# DE-290817_01.net
KiCad netlist of a schematic drawn in Altium Designer
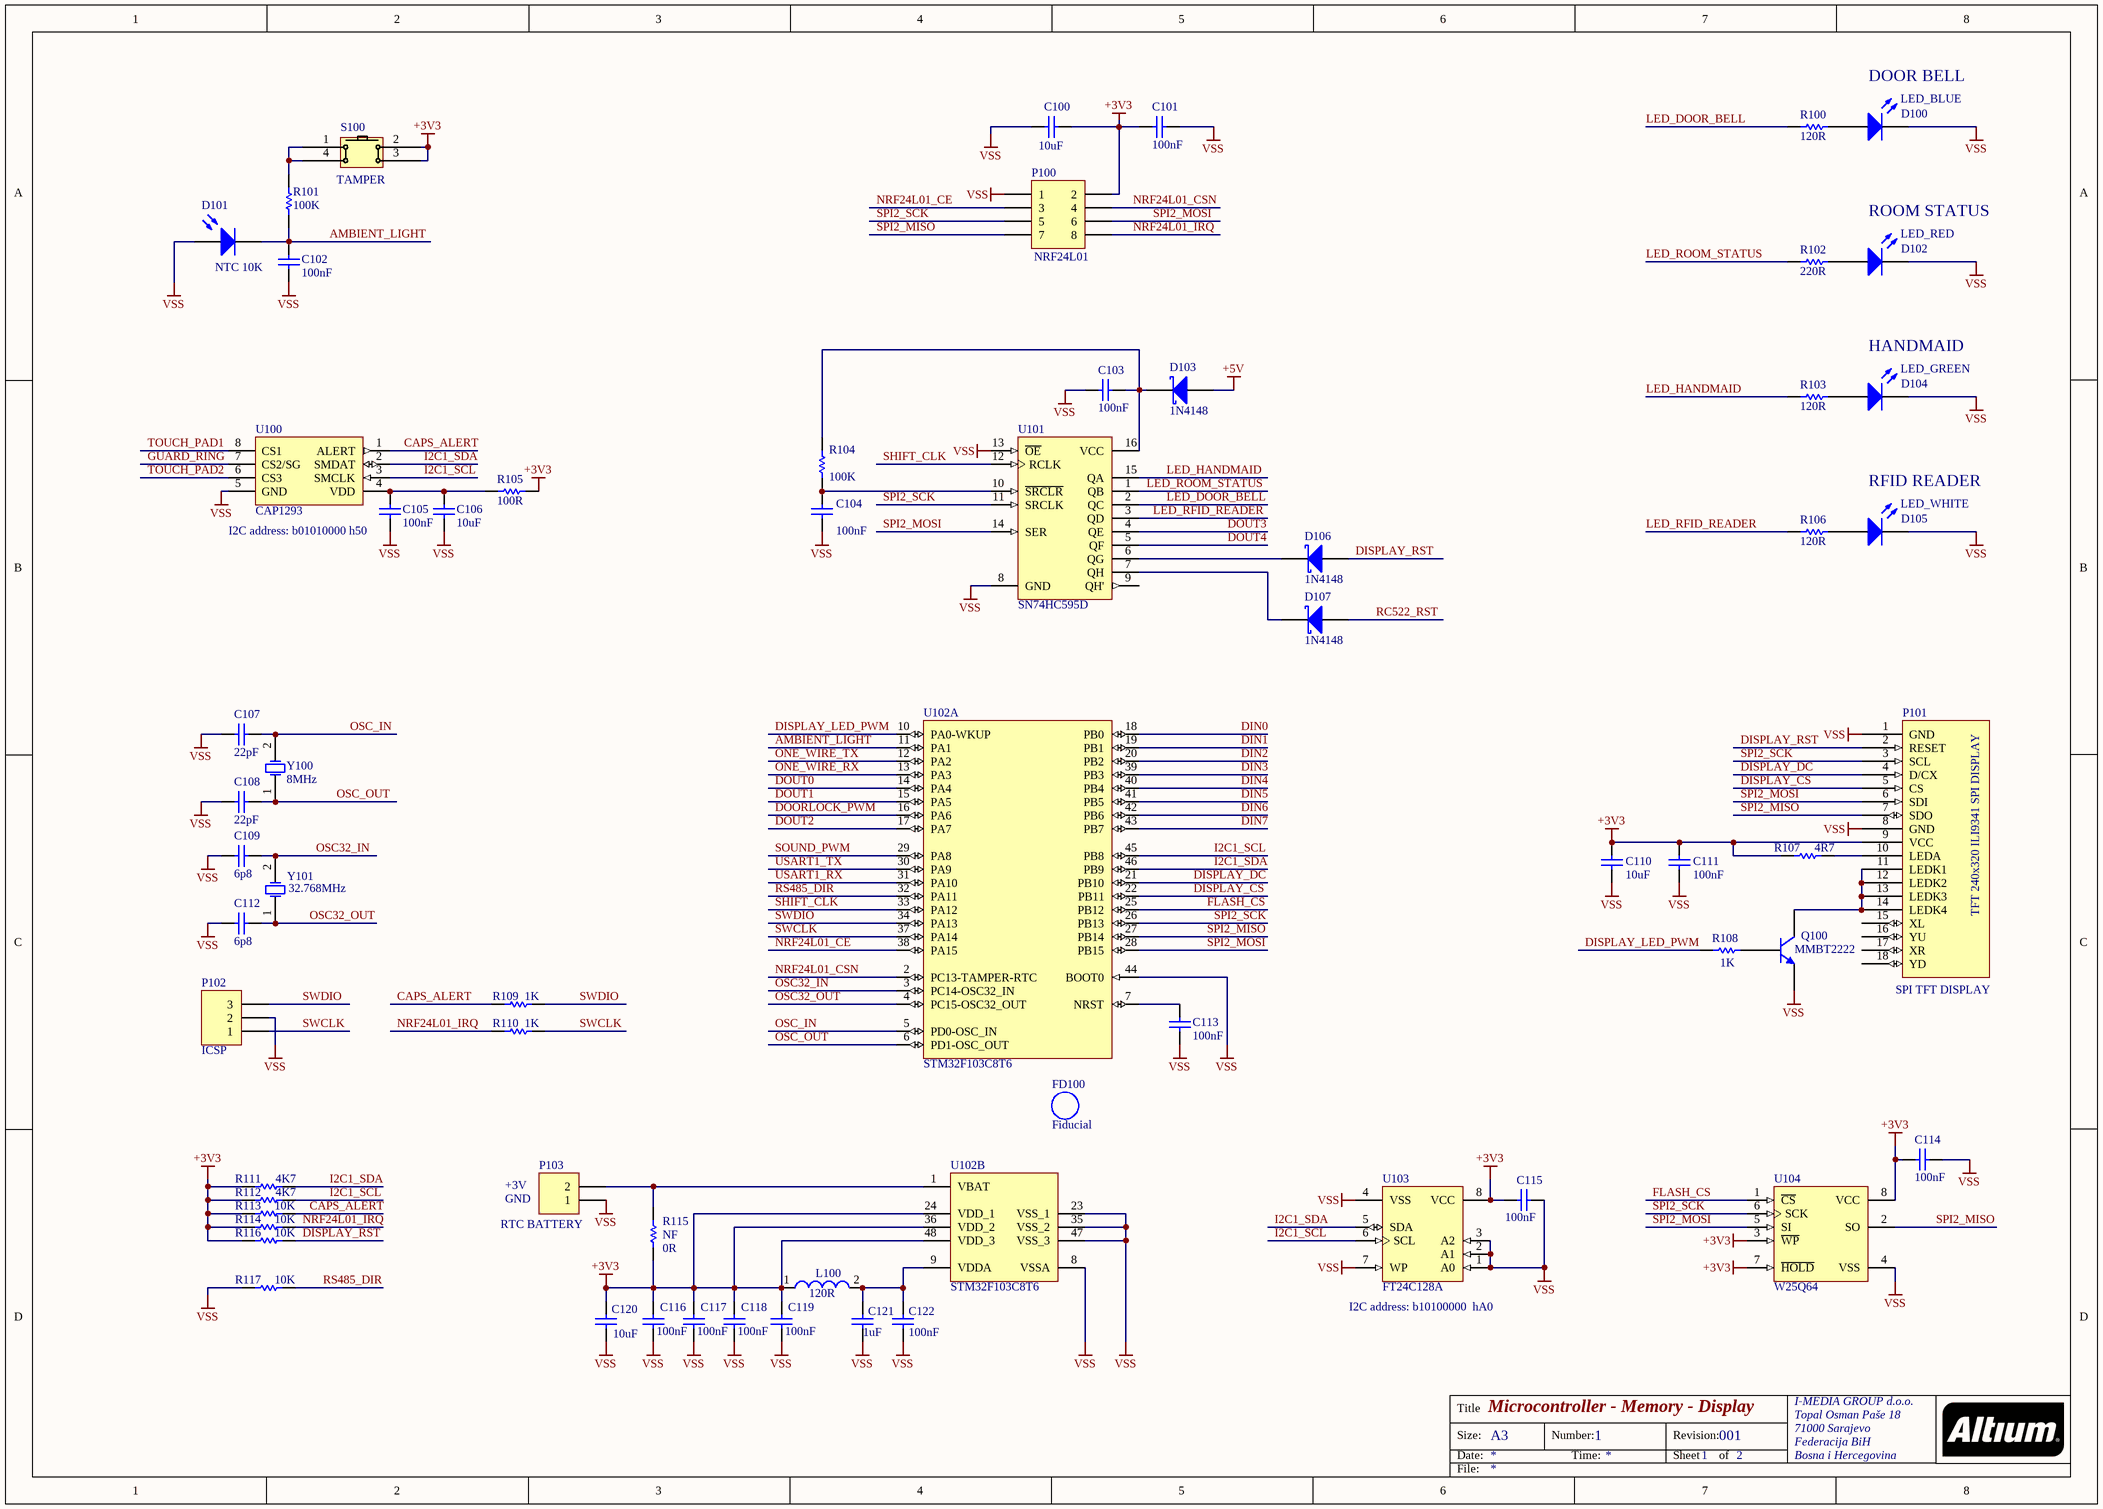
[diagram p0: DE-290817_01.SchDoc]

(export (version "E")
  (design (tool "Eeschema 10.0.6"))
  (components
    (comp (ref "C100")
      (value "10uF")
      (footprint "0805")
      (description "Ceramic Chip Capacitor - Standard")
      (fields (field (name "PUBLISHER") "Altium Limited"))
      (libsource (lib "KEMET Chip Capacitor") (part "C0805"))
    )
    (comp (ref "C101")
      (value "100nF")
      (footprint "0603")
      (description "Ceramic Chip Capacitor - Standard")
      (fields (field (name "PUBLISHER") "Altium Limited"))
      (libsource (lib "DE-290817") (part "C0603"))
    )
    (comp (ref "C102")
      (value "100nF")
      (footprint "0603")
      (description "Ceramic Chip Capacitor - Standard")
      (fields (field (name "PUBLISHER") "Altium Limited"))
      (libsource (lib "DE-290817") (part "C0603"))
    )
    (comp (ref "C103")
      (value "100nF")
      (footprint "0603")
      (description "Ceramic Chip Capacitor - Standard")
      (fields (field (name "PUBLISHER") "Altium Limited"))
      (libsource (lib "DE-251215") (part "C0603"))
    )
    (comp (ref "C104")
      (value "100nF")
      (footprint "0603")
      (description "Ceramic Chip Capacitor - Standard")
      (fields (field (name "PUBLISHER") "Altium Limited"))
      (libsource (lib "DE-251215") (part "C0603"))
    )
    (comp (ref "C105")
      (value "100nF")
      (footprint "0603")
      (description "Ceramic Chip Capacitor - Standard")
      (fields (field (name "PUBLISHER") "Altium Limited"))
      (libsource (lib "KEMET Chip Capacitor") (part "C0603"))
    )
    (comp (ref "C106")
      (value "10uF")
      (footprint "0805")
      (description "Ceramic Chip Capacitor - Standard")
      (fields (field (name "PUBLISHER") "Altium Limited"))
      (libsource (lib "KEMET Chip Capacitor") (part "C0805"))
    )
    (comp (ref "C107")
      (value "22pF")
      (footprint "0603")
      (description "Ceramic Chip Capacitor - Standard")
      (fields (field (name "PUBLISHER") "Altium Limited"))
      (libsource (lib "DE-010116") (part "C0603"))
    )
    (comp (ref "C108")
      (value "22pF")
      (footprint "0603")
      (description "Ceramic Chip Capacitor - Standard")
      (fields (field (name "PUBLISHER") "Altium Limited"))
      (libsource (lib "DE-010116") (part "C0603"))
    )
    (comp (ref "C109")
      (value "6p8")
      (footprint "0603")
      (description "Ceramic Chip Capacitor - Standard")
      (fields (field (name "PUBLISHER") "Altium Limited"))
      (libsource (lib "DE-010116") (part "C0603"))
    )
    (comp (ref "C110")
      (value "10uF")
      (footprint "0805")
      (description "Ceramic Chip Capacitor - Standard")
      (fields (field (name "PUBLISHER") "Altium Limited"))
      (libsource (lib "DE-251215") (part "C0805"))
    )
    (comp (ref "C111")
      (value "100nF")
      (footprint "0603")
      (description "Ceramic Chip Capacitor - Standard")
      (fields (field (name "PUBLISHER") "Altium Limited"))
      (libsource (lib "DE-010116") (part "C0603"))
    )
    (comp (ref "C112")
      (value "6p8")
      (footprint "0603")
      (description "Ceramic Chip Capacitor - Standard")
      (fields (field (name "PUBLISHER") "Altium Limited"))
      (libsource (lib "DE-010116") (part "C0603"))
    )
    (comp (ref "C113")
      (value "100nF")
      (footprint "0603")
      (description "Ceramic Chip Capacitor - Standard")
      (fields (field (name "PUBLISHER") "Altium Limited"))
      (libsource (lib "DE-010116") (part "C0603"))
    )
    (comp (ref "C114")
      (value "100nF")
      (footprint "0603")
      (description "Ceramic Chip Capacitor - Standard")
      (fields (field (name "PUBLISHER") "Altium Limited"))
      (libsource (lib "DE-200216_03") (part "C0603"))
    )
    (comp (ref "C115")
      (value "100nF")
      (footprint "0603")
      (description "Ceramic Chip Capacitor - Standard")
      (fields (field (name "PUBLISHER") "Altium Limited"))
      (libsource (lib "DE-251215") (part "C0603"))
    )
    (comp (ref "C116")
      (value "100nF")
      (footprint "0603")
      (description "Ceramic Chip Capacitor - Standard")
      (fields (field (name "PUBLISHER") "Altium Limited"))
      (libsource (lib "DE-251215") (part "C0603"))
    )
    (comp (ref "C117")
      (value "100nF")
      (footprint "0603")
      (description "Ceramic Chip Capacitor - Standard")
      (fields (field (name "PUBLISHER") "Altium Limited"))
      (libsource (lib "DE-251215") (part "C0603"))
    )
    (comp (ref "C118")
      (value "100nF")
      (footprint "0603")
      (description "Ceramic Chip Capacitor - Standard")
      (fields (field (name "PUBLISHER") "Altium Limited"))
      (libsource (lib "DE-251215") (part "C0603"))
    )
    (comp (ref "C119")
      (value "100nF")
      (footprint "0603")
      (description "Ceramic Chip Capacitor - Standard")
      (fields (field (name "PUBLISHER") "Altium Limited"))
      (libsource (lib "DE-251215") (part "C0603"))
    )
    (comp (ref "C120")
      (value "10uF")
      (footprint "0805")
      (description "Ceramic Chip Capacitor - Standard")
      (fields (field (name "PUBLISHER") "Altium Limited"))
      (libsource (lib "DE-251215") (part "C0805"))
    )
    (comp (ref "C121")
      (value "1uF")
      (footprint "0603")
      (description "Ceramic Chip Capacitor - Standard")
      (fields (field (name "PUBLISHER") "Altium Limited"))
      (libsource (lib "DE-200216_01") (part "C0603"))
    )
    (comp (ref "C122")
      (value "100nF")
      (footprint "0603")
      (description "Ceramic Chip Capacitor - Standard")
      (fields (field (name "PUBLISHER") "Altium Limited"))
      (libsource (lib "DE-200216_01") (part "C0603"))
    )
    (comp (ref "D100")
      (value "LED_BLUE")
      (footprint "1.6X0.8X0.8")
      (description "High Performance Chip LED, Red")
      (fields (field (name "PUBLISHER") "Altium Limited"))
      (libsource (lib "DE-251215") (part "HSMZ-C190"))
    )
    (comp (ref "D101")
      (value "NTC 10K")
      (footprint "PIN2")
      (description "Photosensitive Diode")
      (fields (field (name "PUBLISHER") "Altium Limited"))
      (libsource (lib "Miscellaneous Devices") (part "Photo Sen"))
    )
    (comp (ref "D102")
      (value "LED_RED")
      (footprint "1.6X0.8X0.8")
      (description "High Performance Chip LED, Red")
      (fields (field (name "PUBLISHER") "Altium Limited"))
      (libsource (lib "DE-251215") (part "HSMZ-C190"))
    )
    (comp (ref "D103")
      (value "1N4148")
      (footprint "SOD323")
      (description "Schottky Barrier Diode")
      (fields (field (name "PUBLISHER") "Altium Limited"))
      (libsource (lib "DE-290817") (part "1PS76SB10"))
    )
    (comp (ref "D104")
      (value "LED_GREEN")
      (footprint "1.6X0.8X0.8")
      (description "High Performance Chip LED, Red")
      (fields (field (name "PUBLISHER") "Altium Limited"))
      (libsource (lib "DE-251215") (part "HSMZ-C190"))
    )
    (comp (ref "D105")
      (value "LED_WHITE")
      (footprint "1.6X0.8X0.8")
      (description "High Performance Chip LED, Red")
      (fields (field (name "PUBLISHER") "Altium Limited"))
      (libsource (lib "DE-251215") (part "HSMZ-C190"))
    )
    (comp (ref "D106")
      (value "1N4148")
      (footprint "SOD323")
      (description "Schottky Barrier Diode")
      (fields (field (name "PUBLISHER") "Altium Limited"))
      (libsource (lib "DE-290817") (part "1PS76SB10"))
    )
    (comp (ref "D107")
      (value "1N4148")
      (footprint "SOD323")
      (description "Schottky Barrier Diode")
      (fields (field (name "PUBLISHER") "Altium Limited"))
      (libsource (lib "DE-290817") (part "1PS76SB10"))
    )
    (comp (ref "FD100")
      (value "Fiducial")
      (footprint "Fiducial")
      (description "Fiduchial mark")
      (libsource (lib "DE-200216_02_1") (part "Fiduchial"))
    )
    (comp (ref "L100")
      (value "120R")
      (footprint "SMD-0805")
      (description "SMD EMI Suppression Ferrite Bead WE-CBF, Z = 120 Ohm")
      (libsource (lib "Wuerth Elektronik EMC Ferrite") (part "74279202"))
    )
    (comp (ref "P100")
      (value "NRF24L01")
      (footprint "HDR2X4")
      (description "Header, 4-Pin, Dual row")
      (fields (field (name "PUBLISHER") "Altium Limited"))
      (libsource (lib "Miscellaneous Connectors") (part "Header 4X2"))
    )
    (comp (ref "P101")
      (value "SPI TFT DISPLAY")
      (footprint "DISPLAY CON")
      (description "DISPLAY ILI9341 240x320  CONNECTOR")
      (libsource (lib "DE-290817") (part "DISPLAY CONNECTOR"))
    )
    (comp (ref "P102")
      (value "ICSP")
      (footprint "ICSP")
      (description "ICSP connection pads")
      (libsource (lib "DE-290817") (part "ICSP"))
    )
    (comp (ref "P103")
      (value "RTC BATTERY")
      (footprint "HDR1X2")
      (description "Header, 2-Pin")
      (fields (field (name "PUBLISHER") "Altium Limited"))
      (libsource (lib "Miscellaneous Connectors") (part "Header 2"))
    )
    (comp (ref "Q100")
      (value "MMBT2222")
      (footprint "SOT23_N")
      (description "NPN General-purpose Transistor")
      (fields (field (name "PUBLISHER") "Altium Limited"))
      (libsource (lib "DE-290817") (part "BC817"))
    )
    (comp (ref "R100")
      (value "120R")
      (footprint "ERA-0603")
      (fields (field (name "PUBLISHER") "Altium Limited"))
      (libsource (lib "DE-200216_01") (part "ERAV"))
    )
    (comp (ref "R101")
      (value "100K")
      (footprint "ERA-0603")
      (fields (field (name "PUBLISHER") "Altium Limited"))
      (libsource (lib "DE-290817") (part "ERAV"))
    )
    (comp (ref "R102")
      (value "220R")
      (footprint "ERA-0603")
      (fields (field (name "PUBLISHER") "Altium Limited"))
      (libsource (lib "DE-200216_01") (part "ERAV"))
    )
    (comp (ref "R103")
      (value "120R")
      (footprint "ERA-0603")
      (fields (field (name "PUBLISHER") "Altium Limited"))
      (libsource (lib "DE-200216_01") (part "ERAV"))
    )
    (comp (ref "R104")
      (value "100K")
      (footprint "ERA-0603")
      (fields (field (name "PUBLISHER") "Altium Limited"))
      (libsource (lib "DE-200216_03") (part "ERAV"))
    )
    (comp (ref "R105")
      (value "100R")
      (footprint "ERA-0603")
      (fields (field (name "PUBLISHER") "Altium Limited"))
      (libsource (lib "DE-200216_03") (part "ERAV"))
    )
    (comp (ref "R106")
      (value "120R")
      (footprint "ERA-0603")
      (fields (field (name "PUBLISHER") "Altium Limited"))
      (libsource (lib "DE-200216_01") (part "ERAV"))
    )
    (comp (ref "R107")
      (value "4R7")
      (footprint "ERA-0603")
      (fields (field (name "PUBLISHER") "Altium Limited"))
      (libsource (lib "DE-200216_02_1") (part "ERAV"))
    )
    (comp (ref "R108")
      (value "1K")
      (footprint "ERA-0603")
      (fields (field (name "PUBLISHER") "Altium Limited"))
      (libsource (lib "DE-010116") (part "ERAV"))
    )
    (comp (ref "R109")
      (value "1K")
      (footprint "ERA-0603")
      (fields (field (name "PUBLISHER") "Altium Limited"))
      (libsource (lib "DE-251215") (part "ERAV"))
    )
    (comp (ref "R110")
      (value "1K")
      (footprint "ERA-0603")
      (fields (field (name "PUBLISHER") "Altium Limited"))
      (libsource (lib "DE-251215") (part "ERAV"))
    )
    (comp (ref "R111")
      (value "4K7")
      (footprint "ERA-0603")
      (fields (field (name "PUBLISHER") "Altium Limited"))
      (libsource (lib "DE-251215") (part "ERAV"))
    )
    (comp (ref "R112")
      (value "4K7")
      (footprint "ERA-0603")
      (fields (field (name "PUBLISHER") "Altium Limited"))
      (libsource (lib "DE-251215") (part "ERAV"))
    )
    (comp (ref "R113")
      (value "10K")
      (footprint "ERA-0603")
      (fields (field (name "PUBLISHER") "Altium Limited"))
      (libsource (lib "DE-251215") (part "ERAV"))
    )
    (comp (ref "R114")
      (value "10K")
      (footprint "ERA-0603")
      (fields (field (name "PUBLISHER") "Altium Limited"))
      (libsource (lib "DE-251215") (part "ERAV"))
    )
    (comp (ref "R115")
      (value "NF")
      (footprint "ERA-0603")
      (fields (field (name "ALTIUM_VALUE") "0R") (field (name "PUBLISHER") "Altium Limited"))
      (libsource (lib "DE-251215") (part "ERAV"))
    )
    (comp (ref "R116")
      (value "10K")
      (footprint "ERA-0603")
      (fields (field (name "PUBLISHER") "Altium Limited"))
      (libsource (lib "DE-251215") (part "ERAV"))
    )
    (comp (ref "R117")
      (value "10K")
      (footprint "ERA-0603")
      (fields (field (name "PUBLISHER") "Altium Limited"))
      (libsource (lib "DE-251215") (part "ERAV"))
    )
    (comp (ref "S100")
      (value "TAMPER")
      (footprint "TACTILE_SWITCH")
      (libsource (lib "DE-290817") (part "TACKTILE_SWITCH"))
    )
    (comp (ref "U100")
      (value "CAP1293")
      (footprint "SOP8")
      (description "3-Channel Capacitive Touch Sensor with Proximity Detection & Signal Guard")
      (libsource (lib "DE-290817") (part "CAP1293"))
    )
    (comp (ref "U101")
      (value "SN74HC595D")
      (footprint "D016_N")
      (description "8-Bit Shift Register with 3-State Output Registers")
      (fields (field (name "PUBLISHER") "Altium Limited"))
      (libsource (lib "DE-290817") (part "SN74HC595D"))
    )
    (comp (ref "U102")
      (value "STM32F103C8T6")
      (footprint "STM-LQFP48_N")
      (libsource (lib "STMicroelectronics STM32 F1") (part "STM32F103C8T6"))
    )
    (comp (ref "U103")
      (value "FT24C128A")
      (footprint "SOIC-SN8_N")
      (description "64Kbit, 400kHz, 1.7V, I2C Serial EEPROM, 8-Pin SOIC 150mil, Commercial Temperature")
      (fields (field (name "PUBLISHER") "Altium Limited"))
      (libsource (lib "Microchip Memory I2C Serial EEPROM") (part "24AA64/SN"))
    )
    (comp (ref "U104")
      (value "W25Q64")
      (footprint "SOIJ-SM8_N")
      (description "64K SPI Bus Serial EEPROM, 8-Pin SOIC, Industrial Temperature")
      (fields (field (name "PUBLISHER") "Altium Limited"))
      (libsource (lib "Microchip Memory SPI Serial EEPROM") (part "25LC640A-I/SN"))
    )
    (comp (ref "Y100")
      (value "8MHz")
      (footprint "HC49/4H_SMX")
      (description "Surface Mount Quartz Crystal")
      (fields (field (name "PUBLISHER") "Altium Limited"))
      (libsource (lib "DE-200216_02") (part "HC49/4H_SMX"))
    )
    (comp (ref "Y101")
      (value "32.768MHz")
      (footprint "R26")
      (description "Tuning Fork Crystal Unit")
      (fields (field (name "PUBLISHER") "Altium Limited"))
      (libsource (lib "Raltron Crystal Oscillator") (part "R26-32.768"))
    )
  )
  (nets
    (net (code "1") (name "+3V3") (class "Default")
      (node (ref "C100") (pin "1") (pinfunction "1_1") (pintype "passive"))
      (node (ref "C101") (pin "1") (pinfunction "1_1") (pintype "passive"))
      (node (ref "C110") (pin "2") (pinfunction "2_2") (pintype "passive"))
      (node (ref "C111") (pin "1") (pinfunction "1_1") (pintype "passive"))
      (node (ref "C114") (pin "1") (pinfunction "1_1") (pintype "passive"))
      (node (ref "C115") (pin "1") (pinfunction "1_1") (pintype "passive"))
      (node (ref "C116") (pin "2") (pinfunction "2_2") (pintype "passive"))
      (node (ref "C117") (pin "2") (pinfunction "2_2") (pintype "passive"))
      (node (ref "C118") (pin "2") (pinfunction "2_2") (pintype "passive"))
      (node (ref "C119") (pin "2") (pinfunction "2_2") (pintype "passive"))
      (node (ref "C120") (pin "2") (pinfunction "2_2") (pintype "passive"))
      (node (ref "L100") (pin "1") (pinfunction "1_1") (pintype "passive"))
      (node (ref "P100") (pin "2") (pinfunction "2_2") (pintype "passive"))
      (node (ref "P101") (pin "9") (pinfunction "VCC_9") (pintype "power_in"))
      (node (ref "R105") (pin "2") (pinfunction "2_2") (pintype "passive"))
      (node (ref "R107") (pin "1") (pinfunction "1_1") (pintype "passive"))
      (node (ref "R111") (pin "2") (pinfunction "2_2") (pintype "passive"))
      (node (ref "R112") (pin "2") (pinfunction "2_2") (pintype "passive"))
      (node (ref "R113") (pin "2") (pinfunction "2_2") (pintype "passive"))
      (node (ref "R114") (pin "2") (pinfunction "2_2") (pintype "passive"))
      (node (ref "R115") (pin "2") (pinfunction "2_2") (pintype "passive"))
      (node (ref "R116") (pin "2") (pinfunction "2_2") (pintype "passive"))
      (node (ref "S100") (pin "2") (pinfunction "2_2") (pintype "passive"))
      (node (ref "S100") (pin "3") (pinfunction "3_3") (pintype "passive"))
      (node (ref "U102") (pin "24") (pinfunction "VDD_1_24") (pintype "power_in"))
      (node (ref "U102") (pin "36") (pinfunction "VDD_2_36") (pintype "power_in"))
      (node (ref "U102") (pin "48") (pinfunction "VDD_3_48") (pintype "power_in"))
      (node (ref "U103") (pin "8") (pinfunction "VCC_8") (pintype "power_in"))
      (node (ref "U104") (pin "3") (pinfunction "~{WP}_3") (pintype "input"))
      (node (ref "U104") (pin "7") (pinfunction "~{HOLD}_7") (pintype "input"))
      (node (ref "U104") (pin "8") (pinfunction "VCC_8") (pintype "power_in"))
    )
    (net (code "2") (name "+5V") (class "Default")
      (node (ref "D103") (pin "2") (pinfunction "A_2") (pintype "passive"))
    )
    (net (code "3") (name "/AMBIENT_LIGHT") (class "Default")
      (node (ref "C102") (pin "2") (pinfunction "2_2") (pintype "passive"))
      (node (ref "D101") (pin "2") (pinfunction "K_2") (pintype "passive"))
      (node (ref "R101") (pin "2") (pinfunction "2_2") (pintype "passive"))
      (node (ref "U102") (pin "11") (pinfunction "PA1_11") (pintype "bidirectional"))
    )
    (net (code "4") (name "/CAPS_ALERT") (class "Default")
      (node (ref "R109") (pin "2") (pinfunction "2_2") (pintype "passive"))
      (node (ref "R113") (pin "1") (pinfunction "1_1") (pintype "passive"))
      (node (ref "U100") (pin "1") (pinfunction "ALERT_1") (pintype "output"))
    )
    (net (code "5") (name "/DIN0") (class "Default")
      (node (ref "U102") (pin "18") (pinfunction "PB0_18") (pintype "bidirectional"))
    )
    (net (code "6") (name "/DIN1") (class "Default")
      (node (ref "U102") (pin "19") (pinfunction "PB1_19") (pintype "bidirectional"))
    )
    (net (code "7") (name "/DIN2") (class "Default")
      (node (ref "U102") (pin "20") (pinfunction "PB2_20") (pintype "bidirectional"))
    )
    (net (code "8") (name "/DIN3") (class "Default")
      (node (ref "U102") (pin "39") (pinfunction "PB3_39") (pintype "bidirectional"))
    )
    (net (code "9") (name "/DIN4") (class "Default")
      (node (ref "U102") (pin "40") (pinfunction "PB4_40") (pintype "bidirectional"))
    )
    (net (code "10") (name "/DIN5") (class "Default")
      (node (ref "U102") (pin "41") (pinfunction "PB5_41") (pintype "bidirectional"))
    )
    (net (code "11") (name "/DIN6") (class "Default")
      (node (ref "U102") (pin "42") (pinfunction "PB6_42") (pintype "bidirectional"))
    )
    (net (code "12") (name "/DIN7") (class "Default")
      (node (ref "U102") (pin "43") (pinfunction "PB7_43") (pintype "bidirectional"))
    )
    (net (code "13") (name "/DISPLAY_CS") (class "Default")
      (node (ref "P101") (pin "5") (pinfunction "CS_5") (pintype "input"))
      (node (ref "U102") (pin "22") (pinfunction "PB11_22") (pintype "bidirectional"))
    )
    (net (code "14") (name "/DISPLAY_DC") (class "Default")
      (node (ref "P101") (pin "4") (pinfunction "D/CX_4") (pintype "input"))
      (node (ref "U102") (pin "21") (pinfunction "PB10_21") (pintype "bidirectional"))
    )
    (net (code "15") (name "/DISPLAY_LED_PWM") (class "Default")
      (node (ref "R108") (pin "1") (pinfunction "1_1") (pintype "passive"))
      (node (ref "U102") (pin "10") (pinfunction "PA0-WKUP_10") (pintype "bidirectional"))
    )
    (net (code "16") (name "/DISPLAY_RST") (class "Default")
      (node (ref "D106") (pin "2") (pinfunction "A_2") (pintype "passive"))
      (node (ref "P101") (pin "2") (pinfunction "RESET_2") (pintype "input"))
      (node (ref "R116") (pin "1") (pinfunction "1_1") (pintype "passive"))
    )
    (net (code "17") (name "/DOORLOCK_PWM") (class "Default")
      (node (ref "U102") (pin "16") (pinfunction "PA6_16") (pintype "bidirectional"))
    )
    (net (code "18") (name "/DOUT0") (class "Default")
      (node (ref "U102") (pin "14") (pinfunction "PA4_14") (pintype "bidirectional"))
    )
    (net (code "19") (name "/DOUT1") (class "Default")
      (node (ref "U102") (pin "15") (pinfunction "PA5_15") (pintype "bidirectional"))
    )
    (net (code "20") (name "/DOUT2") (class "Default")
      (node (ref "U102") (pin "17") (pinfunction "PA7_17") (pintype "bidirectional"))
    )
    (net (code "21") (name "/DOUT3") (class "Default")
      (node (ref "U101") (pin "4") (pinfunction "QE_4") (pintype "tri_state"))
    )
    (net (code "22") (name "/DOUT4") (class "Default")
      (node (ref "U101") (pin "5") (pinfunction "QF_5") (pintype "tri_state"))
    )
    (net (code "23") (name "/FLASH_CS") (class "Default")
      (node (ref "U102") (pin "25") (pinfunction "PB12_25") (pintype "bidirectional"))
      (node (ref "U104") (pin "1") (pinfunction "~{CS}_1") (pintype "input"))
    )
    (net (code "24") (name "/GUARD_RING") (class "Default")
      (node (ref "U100") (pin "7") (pinfunction "CS2/SG_7") (pintype "passive"))
    )
    (net (code "25") (name "/I2C1_SCL") (class "Default")
      (node (ref "R112") (pin "1") (pinfunction "1_1") (pintype "passive"))
      (node (ref "U100") (pin "3") (pinfunction "SMCLK_3") (pintype "input"))
      (node (ref "U102") (pin "45") (pinfunction "PB8_45") (pintype "bidirectional"))
      (node (ref "U103") (pin "6") (pinfunction "SCL_6") (pintype "input"))
    )
    (net (code "26") (name "/I2C1_SDA") (class "Default")
      (node (ref "R111") (pin "1") (pinfunction "1_1") (pintype "passive"))
      (node (ref "U100") (pin "2") (pinfunction "SMDAT_2") (pintype "bidirectional"))
      (node (ref "U102") (pin "46") (pinfunction "PB9_46") (pintype "bidirectional"))
      (node (ref "U103") (pin "5") (pinfunction "SDA_5") (pintype "bidirectional"))
    )
    (net (code "27") (name "/LED_DOOR_BELL") (class "Default")
      (node (ref "R100") (pin "2") (pinfunction "2_2") (pintype "passive"))
      (node (ref "U101") (pin "2") (pinfunction "QC_2") (pintype "tri_state"))
    )
    (net (code "28") (name "/LED_HANDMAID") (class "Default")
      (node (ref "R103") (pin "2") (pinfunction "2_2") (pintype "passive"))
      (node (ref "U101") (pin "15") (pinfunction "QA_15") (pintype "tri_state"))
    )
    (net (code "29") (name "/LED_RFID_READER") (class "Default")
      (node (ref "R106") (pin "2") (pinfunction "2_2") (pintype "passive"))
      (node (ref "U101") (pin "3") (pinfunction "QD_3") (pintype "tri_state"))
    )
    (net (code "30") (name "/LED_ROOM_STATUS") (class "Default")
      (node (ref "R102") (pin "2") (pinfunction "2_2") (pintype "passive"))
      (node (ref "U101") (pin "1") (pinfunction "QB_1") (pintype "tri_state"))
    )
    (net (code "31") (name "/NRF24L01_CE") (class "Default")
      (node (ref "P100") (pin "3") (pinfunction "3_3") (pintype "passive"))
      (node (ref "U102") (pin "38") (pinfunction "PA15_38") (pintype "bidirectional"))
    )
    (net (code "32") (name "/NRF24L01_CSN") (class "Default")
      (node (ref "P100") (pin "4") (pinfunction "4_4") (pintype "passive"))
      (node (ref "U102") (pin "2") (pinfunction "PC13-TAMPER-RTC_2") (pintype "bidirectional"))
    )
    (net (code "33") (name "/NRF24L01_IRQ") (class "Default")
      (node (ref "P100") (pin "8") (pinfunction "8_8") (pintype "passive"))
      (node (ref "R110") (pin "2") (pinfunction "2_2") (pintype "passive"))
      (node (ref "R114") (pin "1") (pinfunction "1_1") (pintype "passive"))
    )
    (net (code "34") (name "/ONE_WIRE_RX") (class "Default")
      (node (ref "U102") (pin "13") (pinfunction "PA3_13") (pintype "bidirectional"))
    )
    (net (code "35") (name "/ONE_WIRE_TX") (class "Default")
      (node (ref "U102") (pin "12") (pinfunction "PA2_12") (pintype "bidirectional"))
    )
    (net (code "36") (name "/OSC32_IN") (class "Default")
      (node (ref "C109") (pin "1") (pinfunction "1_1") (pintype "passive"))
      (node (ref "U102") (pin "3") (pinfunction "PC14-OSC32_IN_3") (pintype "bidirectional"))
      (node (ref "Y101") (pin "2") (pinfunction "OSC2_2") (pintype "passive"))
    )
    (net (code "37") (name "/OSC32_OUT") (class "Default")
      (node (ref "C112") (pin "1") (pinfunction "1_1") (pintype "passive"))
      (node (ref "U102") (pin "4") (pinfunction "PC15-OSC32_OUT_4") (pintype "bidirectional"))
      (node (ref "Y101") (pin "1") (pinfunction "OSC1_1") (pintype "passive"))
    )
    (net (code "38") (name "/OSC_IN") (class "Default")
      (node (ref "C107") (pin "1") (pinfunction "1_1") (pintype "passive"))
      (node (ref "U102") (pin "5") (pinfunction "PD0-OSC_IN_5") (pintype "bidirectional"))
      (node (ref "Y100") (pin "2") (pinfunction "OSC2_2") (pintype "passive"))
    )
    (net (code "39") (name "/OSC_OUT") (class "Default")
      (node (ref "C108") (pin "1") (pinfunction "1_1") (pintype "passive"))
      (node (ref "U102") (pin "6") (pinfunction "PD1-OSC_OUT_6") (pintype "bidirectional"))
      (node (ref "Y100") (pin "1") (pinfunction "OSC1_1") (pintype "passive"))
    )
    (net (code "40") (name "/RC522_RST") (class "Default")
      (node (ref "D107") (pin "2") (pinfunction "A_2") (pintype "passive"))
    )
    (net (code "41") (name "/RS485_DIR") (class "Default")
      (node (ref "R117") (pin "1") (pinfunction "1_1") (pintype "passive"))
      (node (ref "U102") (pin "32") (pinfunction "PA11_32") (pintype "bidirectional"))
    )
    (net (code "42") (name "/SHIFT_CLK") (class "Default")
      (node (ref "U101") (pin "12") (pinfunction "RCLK_12") (pintype "input"))
      (node (ref "U102") (pin "33") (pinfunction "PA12_33") (pintype "bidirectional"))
    )
    (net (code "43") (name "/SOUND_PWM") (class "Default")
      (node (ref "U102") (pin "29") (pinfunction "PA8_29") (pintype "bidirectional"))
    )
    (net (code "44") (name "/SPI2_MISO") (class "Default")
      (node (ref "P100") (pin "7") (pinfunction "7_7") (pintype "passive"))
      (node (ref "P101") (pin "7") (pinfunction "SDO_7") (pintype "bidirectional"))
      (node (ref "U102") (pin "27") (pinfunction "PB14_27") (pintype "bidirectional"))
      (node (ref "U104") (pin "2") (pinfunction "SO_2") (pintype "tri_state"))
    )
    (net (code "45") (name "/SPI2_MOSI") (class "Default")
      (node (ref "P100") (pin "6") (pinfunction "6_6") (pintype "passive"))
      (node (ref "P101") (pin "6") (pinfunction "SDI_6") (pintype "input"))
      (node (ref "U101") (pin "14") (pinfunction "SER_14") (pintype "input"))
      (node (ref "U102") (pin "28") (pinfunction "PB15_28") (pintype "bidirectional"))
      (node (ref "U104") (pin "5") (pinfunction "SI_5") (pintype "input"))
    )
    (net (code "46") (name "/SPI2_SCK") (class "Default")
      (node (ref "P100") (pin "5") (pinfunction "5_5") (pintype "passive"))
      (node (ref "P101") (pin "3") (pinfunction "SCL_3") (pintype "input"))
      (node (ref "U101") (pin "11") (pinfunction "SRCLK_11") (pintype "input"))
      (node (ref "U102") (pin "26") (pinfunction "PB13_26") (pintype "bidirectional"))
      (node (ref "U104") (pin "6") (pinfunction "SCK_6") (pintype "input"))
    )
    (net (code "47") (name "/SWCLK") (class "Default")
      (node (ref "P102") (pin "1") (pinfunction "1_1") (pintype "passive"))
      (node (ref "R110") (pin "1") (pinfunction "1_1") (pintype "passive"))
      (node (ref "U102") (pin "37") (pinfunction "PA14_37") (pintype "bidirectional"))
    )
    (net (code "48") (name "/SWDIO") (class "Default")
      (node (ref "P102") (pin "3") (pinfunction "3_3") (pintype "passive"))
      (node (ref "R109") (pin "1") (pinfunction "1_1") (pintype "passive"))
      (node (ref "U102") (pin "34") (pinfunction "PA13_34") (pintype "bidirectional"))
    )
    (net (code "49") (name "/TOUCH_PAD1") (class "Default")
      (node (ref "U100") (pin "8") (pinfunction "CS1_8") (pintype "passive"))
    )
    (net (code "50") (name "/TOUCH_PAD2") (class "Default")
      (node (ref "U100") (pin "6") (pinfunction "CS3_6") (pintype "passive"))
    )
    (net (code "51") (name "/USART1_RX") (class "Default")
      (node (ref "U102") (pin "31") (pinfunction "PA10_31") (pintype "bidirectional"))
    )
    (net (code "52") (name "/USART1_TX") (class "Default")
      (node (ref "U102") (pin "30") (pinfunction "PA9_30") (pintype "bidirectional"))
    )
    (net (code "53") (name "Net-(D100-A)") (class "Default")
      (node (ref "D100") (pin "1") (pinfunction "A_1") (pintype "passive"))
      (node (ref "R100") (pin "1") (pinfunction "1_1") (pintype "passive"))
    )
    (net (code "54") (name "Net-(D102-A)") (class "Default")
      (node (ref "D102") (pin "1") (pinfunction "A_1") (pintype "passive"))
      (node (ref "R102") (pin "1") (pinfunction "1_1") (pintype "passive"))
    )
    (net (code "55") (name "Net-(D103-K)") (class "Default")
      (node (ref "C103") (pin "1") (pinfunction "1_1") (pintype "passive"))
      (node (ref "D103") (pin "1") (pinfunction "K_1") (pintype "passive"))
      (node (ref "R104") (pin "1") (pinfunction "1_1") (pintype "passive"))
      (node (ref "U101") (pin "16") (pinfunction "VCC_16") (pintype "power_in"))
    )
    (net (code "56") (name "Net-(D104-A)") (class "Default")
      (node (ref "D104") (pin "1") (pinfunction "A_1") (pintype "passive"))
      (node (ref "R103") (pin "1") (pinfunction "1_1") (pintype "passive"))
    )
    (net (code "57") (name "Net-(D105-A)") (class "Default")
      (node (ref "D105") (pin "1") (pinfunction "A_1") (pintype "passive"))
      (node (ref "R106") (pin "1") (pinfunction "1_1") (pintype "passive"))
    )
    (net (code "58") (name "Net-(D106-K)") (class "Default")
      (node (ref "D106") (pin "1") (pinfunction "K_1") (pintype "passive"))
      (node (ref "U101") (pin "6") (pinfunction "QG_6") (pintype "tri_state"))
    )
    (net (code "59") (name "Net-(D107-K)") (class "Default")
      (node (ref "D107") (pin "1") (pinfunction "K_1") (pintype "passive"))
      (node (ref "U101") (pin "7") (pinfunction "QH_7") (pintype "tri_state"))
    )
    (net (code "60") (name "Net-(P101-LEDA)") (class "Default")
      (node (ref "P101") (pin "10") (pinfunction "LEDA_10") (pintype "power_in"))
      (node (ref "R107") (pin "2") (pinfunction "2_2") (pintype "passive"))
    )
    (net (code "61") (name "Net-(P101-LEDK1)") (class "Default")
      (node (ref "P101") (pin "11") (pinfunction "LEDK1_11") (pintype "power_in"))
      (node (ref "P101") (pin "12") (pinfunction "LEDK2_12") (pintype "power_in"))
      (node (ref "P101") (pin "13") (pinfunction "LEDK3_13") (pintype "power_in"))
      (node (ref "P101") (pin "14") (pinfunction "LEDK4_14") (pintype "power_in"))
      (node (ref "Q100") (pin "3") (pinfunction "C_3") (pintype "passive"))
    )
    (net (code "62") (name "Net-(Q100-B)") (class "Default")
      (node (ref "Q100") (pin "1") (pinfunction "B_1") (pintype "passive"))
      (node (ref "R108") (pin "2") (pinfunction "2_2") (pintype "passive"))
    )
    (net (code "63") (name "Net-(R101-Pad1)") (class "Default")
      (node (ref "R101") (pin "1") (pinfunction "1_1") (pintype "passive"))
      (node (ref "S100") (pin "1") (pinfunction "1_1") (pintype "passive"))
      (node (ref "S100") (pin "4") (pinfunction "4_4") (pintype "passive"))
    )
    (net (code "64") (name "Net-(U100-VDD)") (class "Default")
      (node (ref "C105") (pin "1") (pinfunction "1_1") (pintype "passive"))
      (node (ref "C106") (pin "2") (pinfunction "2_2") (pintype "passive"))
      (node (ref "R105") (pin "1") (pinfunction "1_1") (pintype "passive"))
      (node (ref "U100") (pin "4") (pinfunction "VDD_4") (pintype "power_in"))
    )
    (net (code "65") (name "Net-(U101-~{SRCLR})") (class "Default")
      (node (ref "C104") (pin "2") (pinfunction "2_2") (pintype "passive"))
      (node (ref "R104") (pin "2") (pinfunction "2_2") (pintype "passive"))
      (node (ref "U101") (pin "10") (pinfunction "~{SRCLR}_10") (pintype "input"))
    )
    (net (code "66") (name "Net-(U102A-NRST)") (class "Default")
      (node (ref "C113") (pin "1") (pinfunction "1_1") (pintype "passive"))
      (node (ref "U102") (pin "7") (pinfunction "NRST_7") (pintype "bidirectional"))
    )
    (net (code "67") (name "Net-(U102B-VBAT)") (class "Default")
      (node (ref "P103") (pin "2") (pinfunction "2_2") (pintype "passive"))
      (node (ref "R115") (pin "1") (pinfunction "1_1") (pintype "passive"))
      (node (ref "U102") (pin "1") (pinfunction "VBAT_1") (pintype "power_in"))
    )
    (net (code "68") (name "Net-(U102B-VDDA)") (class "Default")
      (node (ref "C121") (pin "2") (pinfunction "2_2") (pintype "passive"))
      (node (ref "C122") (pin "2") (pinfunction "2_2") (pintype "passive"))
      (node (ref "L100") (pin "2") (pinfunction "2_2") (pintype "passive"))
      (node (ref "U102") (pin "9") (pinfunction "VDDA_9") (pintype "power_in"))
    )
    (net (code "69") (name "VSS") (class "Default")
      (node (ref "C100") (pin "2") (pinfunction "2_2") (pintype "passive"))
      (node (ref "C101") (pin "2") (pinfunction "2_2") (pintype "passive"))
      (node (ref "C102") (pin "1") (pinfunction "1_1") (pintype "passive"))
      (node (ref "C103") (pin "2") (pinfunction "2_2") (pintype "passive"))
      (node (ref "C104") (pin "1") (pinfunction "1_1") (pintype "passive"))
      (node (ref "C105") (pin "2") (pinfunction "2_2") (pintype "passive"))
      (node (ref "C106") (pin "1") (pinfunction "1_1") (pintype "passive"))
      (node (ref "C107") (pin "2") (pinfunction "2_2") (pintype "passive"))
      (node (ref "C108") (pin "2") (pinfunction "2_2") (pintype "passive"))
      (node (ref "C109") (pin "2") (pinfunction "2_2") (pintype "passive"))
      (node (ref "C110") (pin "1") (pinfunction "1_1") (pintype "passive"))
      (node (ref "C111") (pin "2") (pinfunction "2_2") (pintype "passive"))
      (node (ref "C112") (pin "2") (pinfunction "2_2") (pintype "passive"))
      (node (ref "C113") (pin "2") (pinfunction "2_2") (pintype "passive"))
      (node (ref "C114") (pin "2") (pinfunction "2_2") (pintype "passive"))
      (node (ref "C115") (pin "2") (pinfunction "2_2") (pintype "passive"))
      (node (ref "C116") (pin "1") (pinfunction "1_1") (pintype "passive"))
      (node (ref "C117") (pin "1") (pinfunction "1_1") (pintype "passive"))
      (node (ref "C118") (pin "1") (pinfunction "1_1") (pintype "passive"))
      (node (ref "C119") (pin "1") (pinfunction "1_1") (pintype "passive"))
      (node (ref "C120") (pin "1") (pinfunction "1_1") (pintype "passive"))
      (node (ref "C121") (pin "1") (pinfunction "1_1") (pintype "passive"))
      (node (ref "C122") (pin "1") (pinfunction "1_1") (pintype "passive"))
      (node (ref "D100") (pin "2") (pinfunction "K_2") (pintype "passive"))
      (node (ref "D101") (pin "1") (pinfunction "A_1") (pintype "passive"))
      (node (ref "D102") (pin "2") (pinfunction "K_2") (pintype "passive"))
      (node (ref "D104") (pin "2") (pinfunction "K_2") (pintype "passive"))
      (node (ref "D105") (pin "2") (pinfunction "K_2") (pintype "passive"))
      (node (ref "P100") (pin "1") (pinfunction "1_1") (pintype "passive"))
      (node (ref "P101") (pin "1") (pinfunction "GND_1") (pintype "power_in"))
      (node (ref "P101") (pin "8") (pinfunction "GND_8") (pintype "power_in"))
      (node (ref "P102") (pin "2") (pinfunction "2_2") (pintype "passive"))
      (node (ref "P103") (pin "1") (pinfunction "1_1") (pintype "passive"))
      (node (ref "Q100") (pin "2") (pinfunction "E_2") (pintype "passive"))
      (node (ref "R117") (pin "2") (pinfunction "2_2") (pintype "passive"))
      (node (ref "U100") (pin "5") (pinfunction "GND_5") (pintype "power_in"))
      (node (ref "U101") (pin "13") (pinfunction "~{OE}_13") (pintype "input"))
      (node (ref "U101") (pin "8") (pinfunction "GND_8") (pintype "power_in"))
      (node (ref "U102") (pin "23") (pinfunction "VSS_1_23") (pintype "power_in"))
      (node (ref "U102") (pin "35") (pinfunction "VSS_2_35") (pintype "power_in"))
      (node (ref "U102") (pin "44") (pinfunction "BOOT0_44") (pintype "input"))
      (node (ref "U102") (pin "47") (pinfunction "VSS_3_47") (pintype "power_in"))
      (node (ref "U102") (pin "8") (pinfunction "VSSA_8") (pintype "power_in"))
      (node (ref "U103") (pin "1") (pinfunction "A0_1") (pintype "input"))
      (node (ref "U103") (pin "2") (pinfunction "A1_2") (pintype "input"))
      (node (ref "U103") (pin "3") (pinfunction "A2_3") (pintype "input"))
      (node (ref "U103") (pin "4") (pinfunction "VSS_4") (pintype "power_in"))
      (node (ref "U103") (pin "7") (pinfunction "WP_7") (pintype "input"))
      (node (ref "U104") (pin "4") (pinfunction "VSS_4") (pintype "power_in"))
    )
    (net (code "70") (name "unconnected-(P101-XL-Pad15)") (class "Default")
      (node (ref "P101") (pin "15") (pinfunction "XL_15") (pintype "bidirectional"))
    )
    (net (code "71") (name "unconnected-(P101-XR-Pad17)") (class "Default")
      (node (ref "P101") (pin "17") (pinfunction "XR_17") (pintype "bidirectional"))
    )
    (net (code "72") (name "unconnected-(P101-YD-Pad18)") (class "Default")
      (node (ref "P101") (pin "18") (pinfunction "YD_18") (pintype "bidirectional"))
    )
    (net (code "73") (name "unconnected-(P101-YU-Pad16)") (class "Default")
      (node (ref "P101") (pin "16") (pinfunction "YU_16") (pintype "bidirectional"))
    )
    (net (code "74") (name "unconnected-(U101-QH'-Pad9)") (class "Default")
      (node (ref "U101") (pin "9") (pinfunction "QH'_9") (pintype "output"))
    )
  )
)
